# Power_Switching_Circuit_rev3.net
KiCad netlist of a schematic drawn in EAGLE
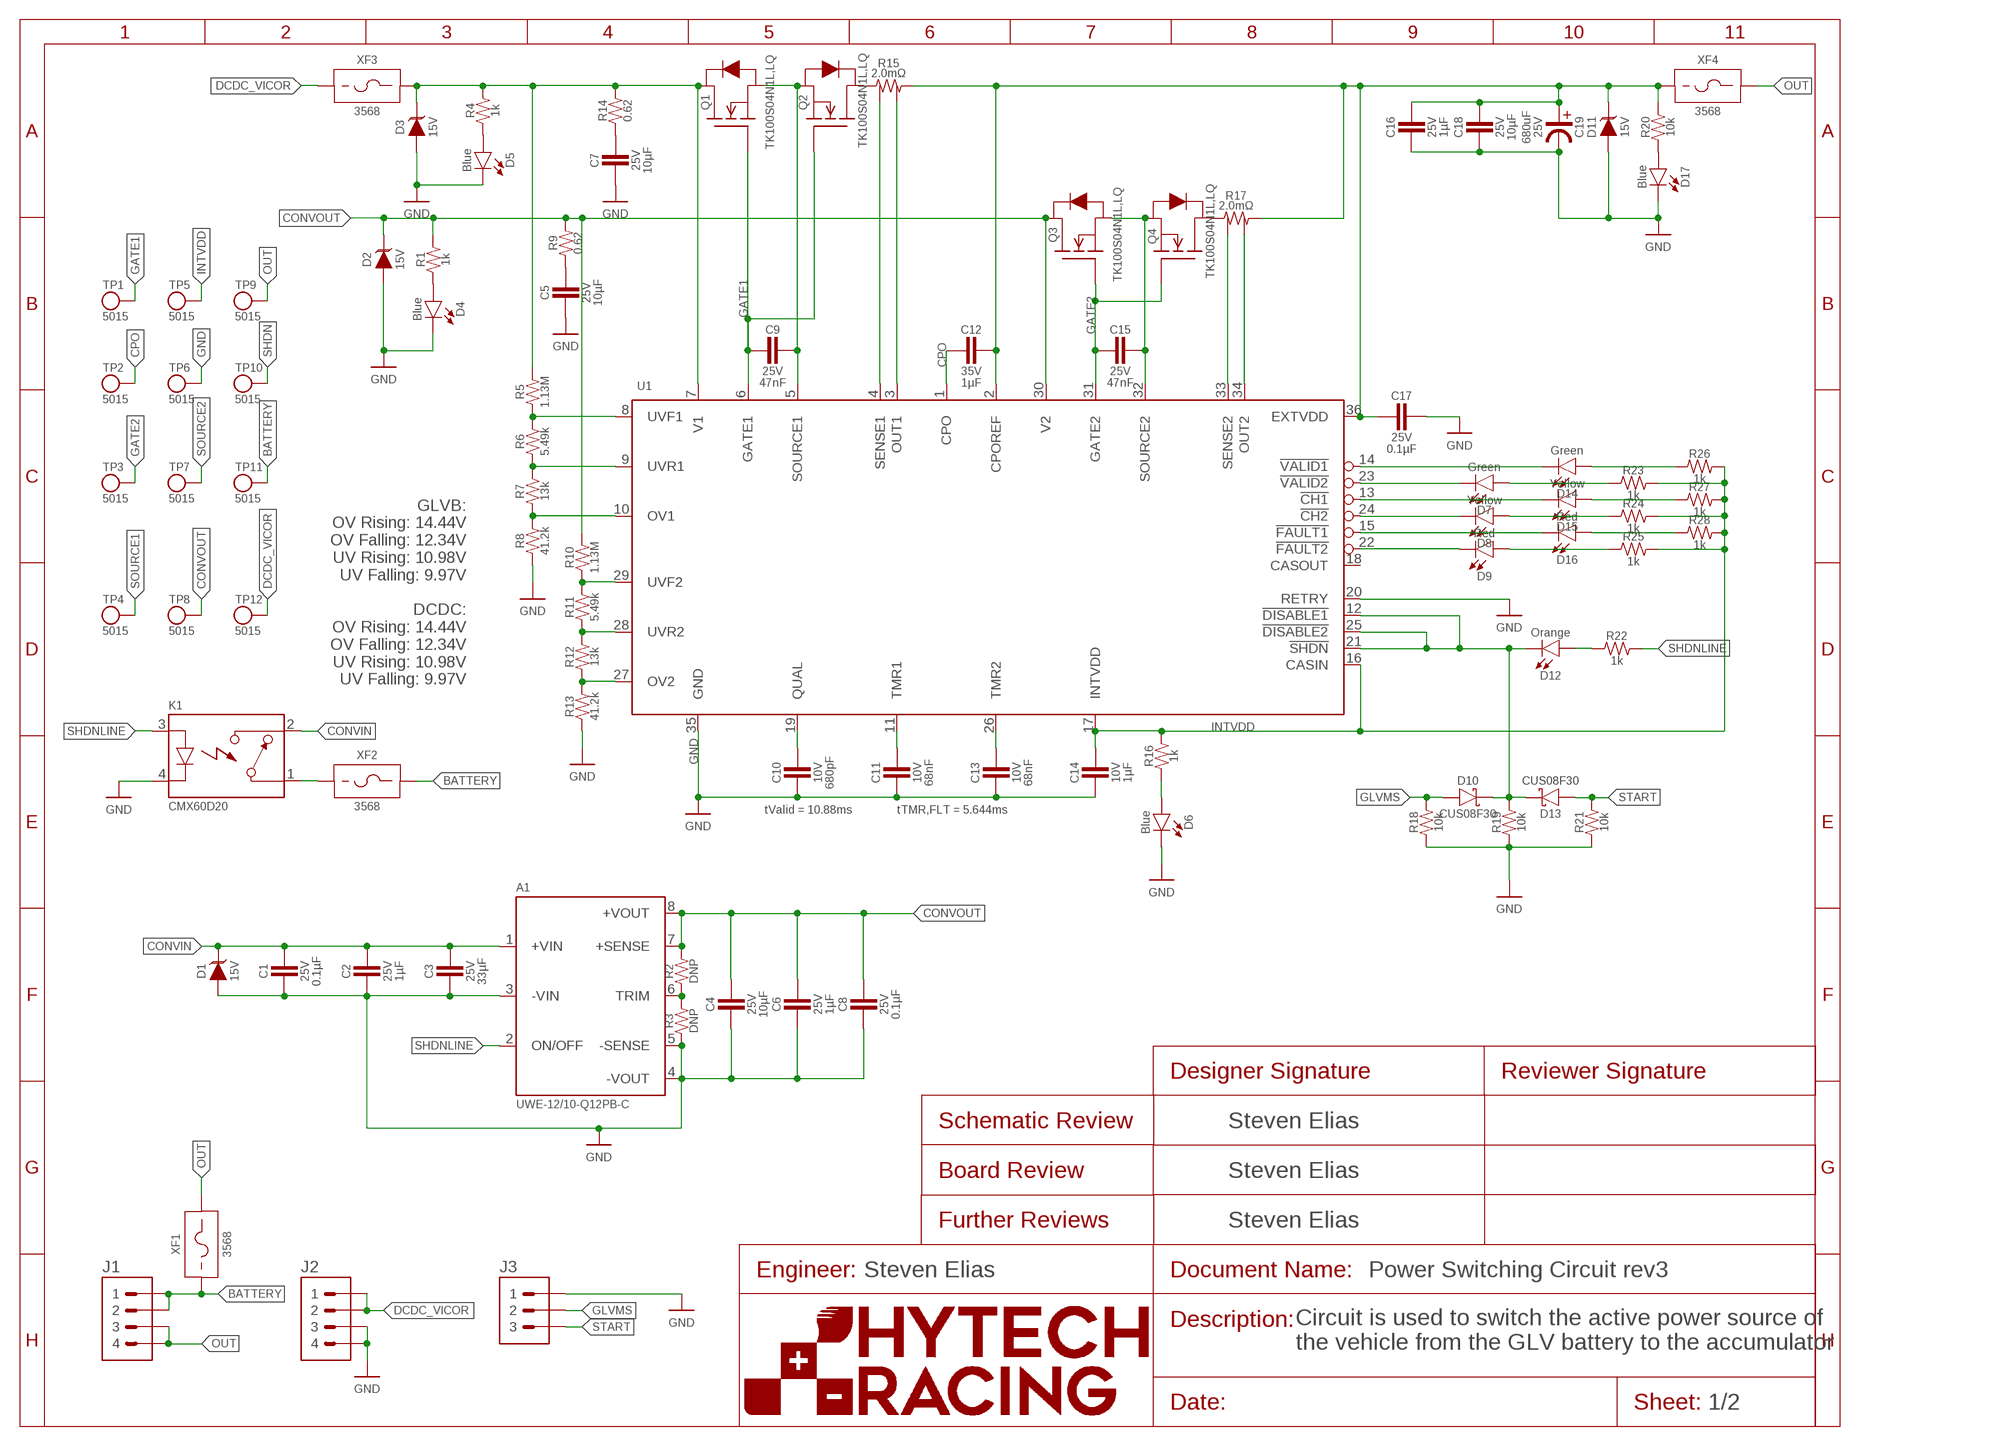
[diagram p0: schematic, sheet 1]
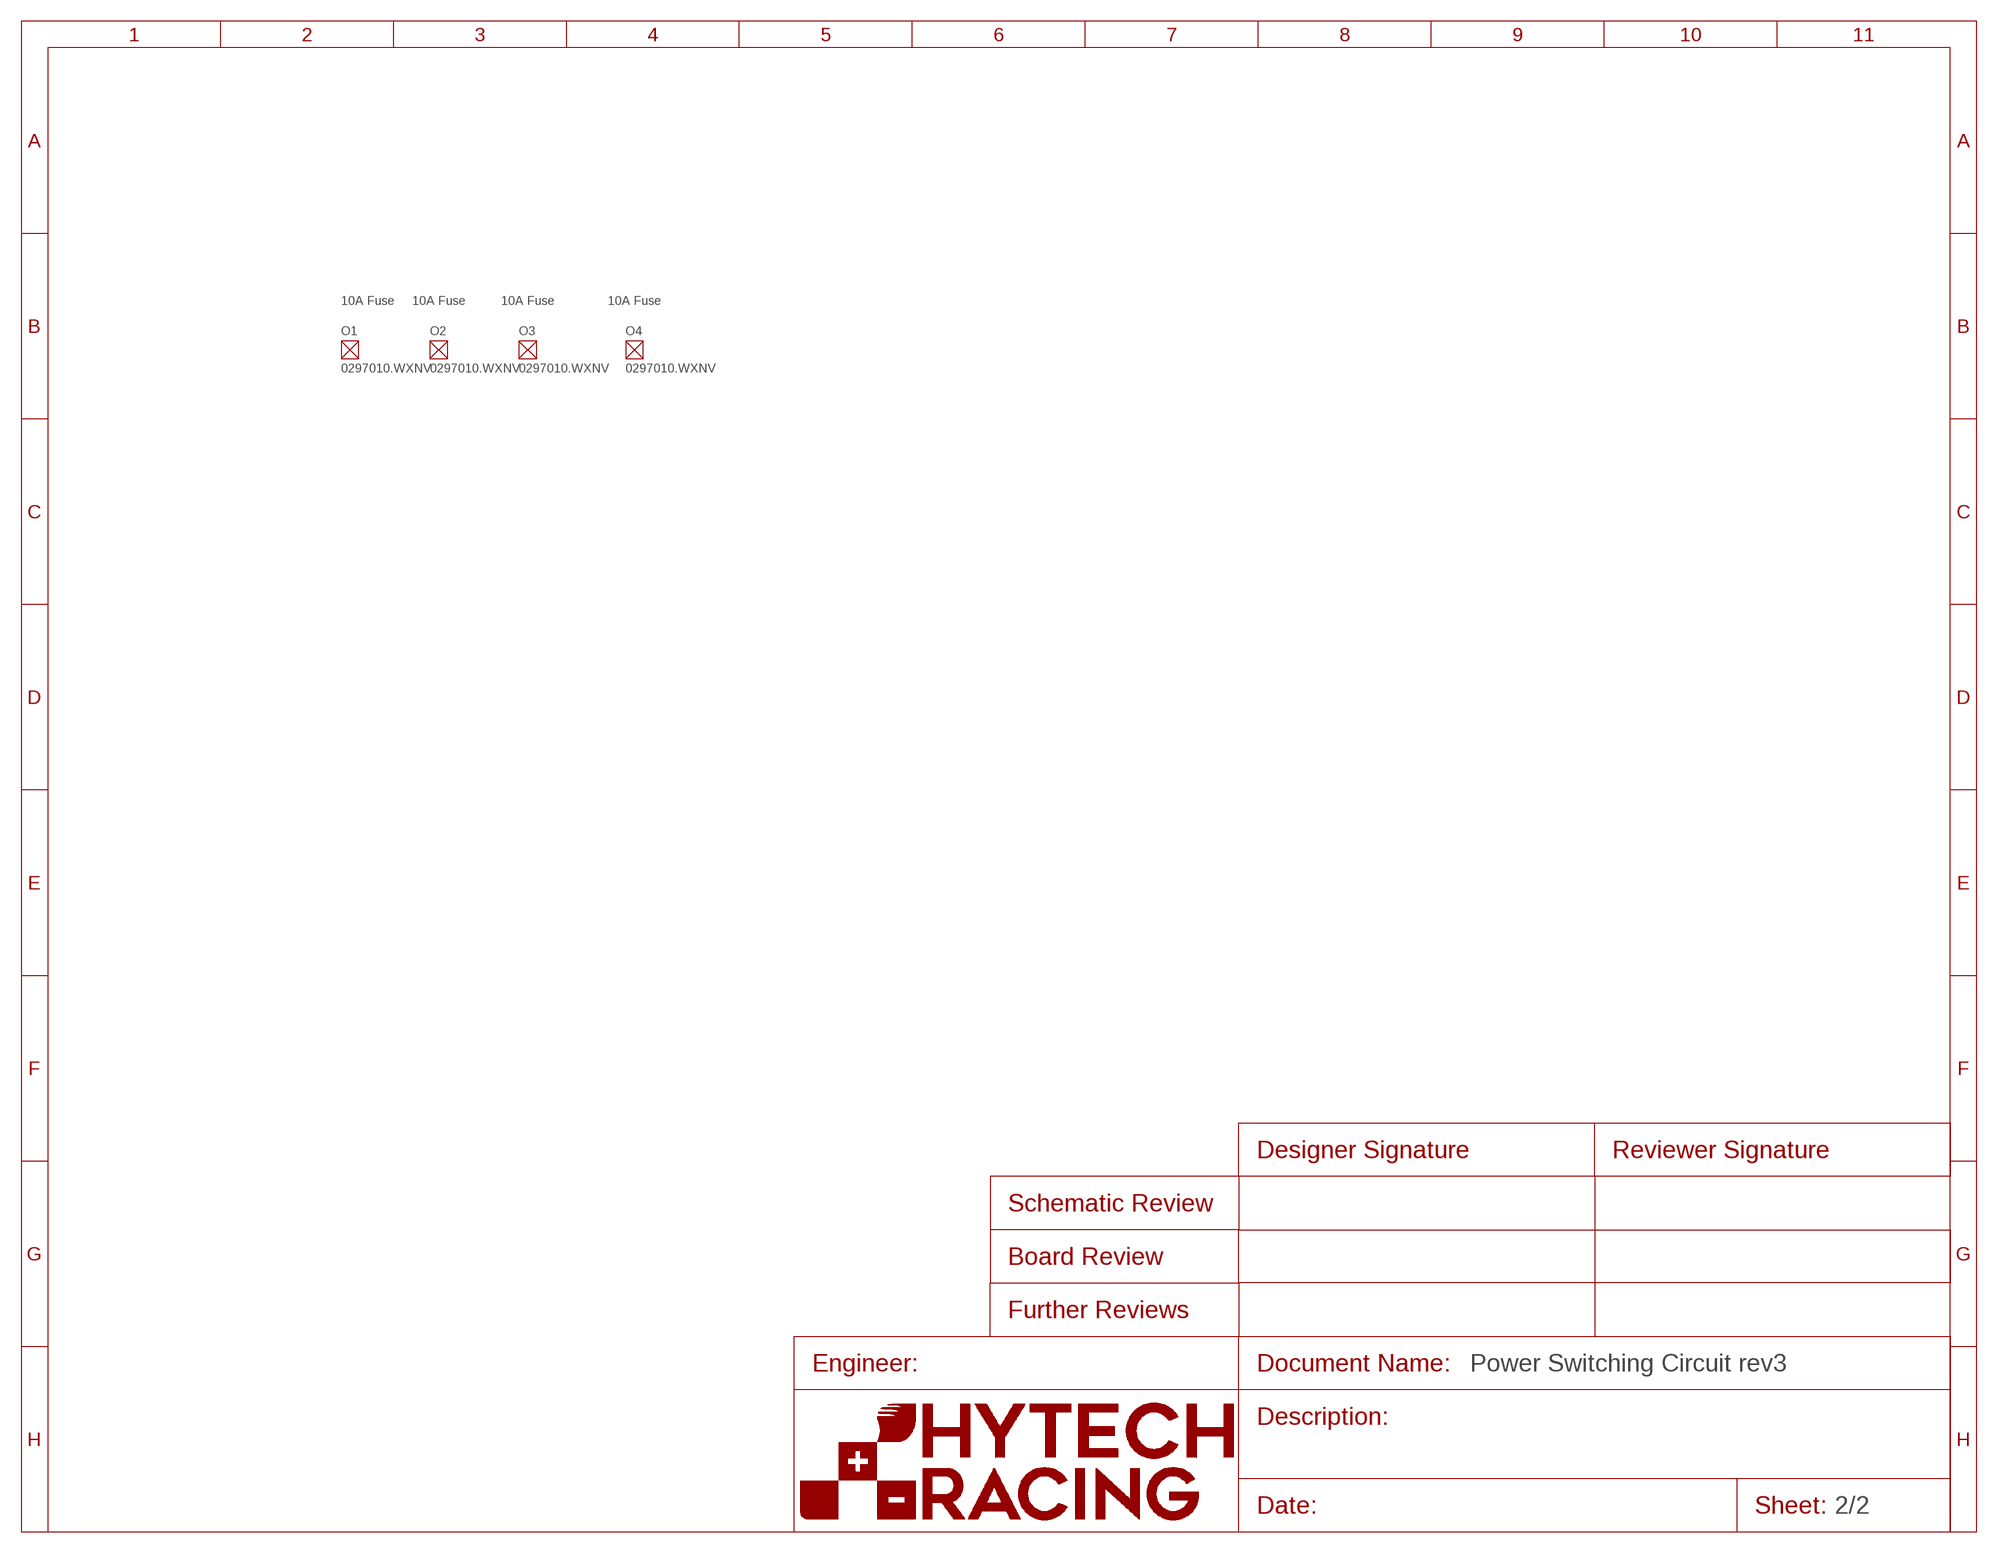
[diagram p1: schematic, sheet 2]

(export (version "E")
  (design (tool "Eeschema 10.0.6"))
  (components
    (comp (ref "A1")
      (value "UWE-12/10-Q12PB-C")
      (footprint "eagle-import:UWE-_")
      (fields
        (field (name "MANUFACTURER") "Murata Power Solutions Inc.")
        (field (name "MPN") "UWE-12/10-Q12PB-C")
      )
      (libsource (lib "eagle-import") (part "UWE-12/10-Q12PB-C"))
    )
    (comp (ref "C1")
      (value "CAPACITOR_0603_25V_0.1UF")
      (footprint "eagle-import:0603-CAP")
      (fields
        (field (name "CAPACITANCE") "0.1µF")
        (field (name "MANUFACTURER") "Samsung Electro-Mechanics")
        (field (name "MPN") "CL10B104KA8NNNC")
        (field (name "TOLERANCE") "10%")
        (field (name "VOLTAGE") "25V")
      )
      (libsource (lib "eagle-import") (part "CAPACITOR_?_060325V_0.1UF"))
    )
    (comp (ref "C2")
      (value "CAPACITOR_0603_25V_1UF")
      (footprint "eagle-import:0603-CAP")
      (fields
        (field (name "CAPACITANCE") "1µF")
        (field (name "MANUFACTURER") "Samsung Electro-Mechanics")
        (field (name "MPN") "CL10B105KA8NNNC")
        (field (name "TOLERANCE") "10%")
        (field (name "VOLTAGE") "25V")
      )
      (libsource (lib "eagle-import") (part "CAPACITOR_?_060325V_1UF"))
    )
    (comp (ref "C3")
      (value "CAPACITOR_1206_25V_33UF")
      (footprint "eagle-import:1206-CAP")
      (fields
        (field (name "CAPACITANCE") "33µF")
        (field (name "MANUFACTURER") "TDK Corporation")
        (field (name "MPN") "C3216X5R1E336M160AC")
        (field (name "TOLERANCE") "20%")
        (field (name "VOLTAGE") "25V")
      )
      (libsource (lib "eagle-import") (part "CAPACITOR_?_120625V_33UF"))
    )
    (comp (ref "C4")
      (value "CAPACITOR_0603_25V_10UF")
      (footprint "eagle-import:0603-CAP")
      (fields
        (field (name "CAPACITANCE") "10µF")
        (field (name "MANUFACTURER") "Murata Electronics")
        (field (name "MPN") "GRM188R61E106MA73D")
        (field (name "TOLERANCE") "20%")
        (field (name "VOLTAGE") "25V")
      )
      (libsource (lib "eagle-import") (part "CAPACITOR_?_060325V_10UF"))
    )
    (comp (ref "C5")
      (value "CAPACITOR_0603_25V_10UF")
      (footprint "eagle-import:0603-CAP")
      (fields
        (field (name "CAPACITANCE") "10µF")
        (field (name "MANUFACTURER") "Murata Electronics")
        (field (name "MPN") "GRM188R61E106MA73D")
        (field (name "TOLERANCE") "20%")
        (field (name "VOLTAGE") "25V")
      )
      (libsource (lib "eagle-import") (part "CAPACITOR_?_060325V_10UF"))
    )
    (comp (ref "C6")
      (value "CAPACITOR_0603_25V_1UF")
      (footprint "eagle-import:0603-CAP")
      (fields
        (field (name "CAPACITANCE") "1µF")
        (field (name "MANUFACTURER") "Samsung Electro-Mechanics")
        (field (name "MPN") "CL10B105KA8NNNC")
        (field (name "TOLERANCE") "10%")
        (field (name "VOLTAGE") "25V")
      )
      (libsource (lib "eagle-import") (part "CAPACITOR_?_060325V_1UF"))
    )
    (comp (ref "C7")
      (value "CAPACITOR_0603_25V_10UF")
      (footprint "eagle-import:0603-CAP")
      (fields
        (field (name "CAPACITANCE") "10µF")
        (field (name "MANUFACTURER") "Murata Electronics")
        (field (name "MPN") "GRM188R61E106MA73D")
        (field (name "TOLERANCE") "20%")
        (field (name "VOLTAGE") "25V")
      )
      (libsource (lib "eagle-import") (part "CAPACITOR_?_060325V_10UF"))
    )
    (comp (ref "C8")
      (value "CAPACITOR_0603_25V_0.1UF")
      (footprint "eagle-import:0603-CAP")
      (fields
        (field (name "CAPACITANCE") "0.1µF")
        (field (name "MANUFACTURER") "Samsung Electro-Mechanics")
        (field (name "MPN") "CL10B104KA8NNNC")
        (field (name "TOLERANCE") "10%")
        (field (name "VOLTAGE") "25V")
      )
      (libsource (lib "eagle-import") (part "CAPACITOR_?_060325V_0.1UF"))
    )
    (comp (ref "C9")
      (value "CAPACITOR_0603_25V_47NF")
      (footprint "eagle-import:0603-CAP")
      (fields
        (field (name "CAPACITANCE") "47nF")
        (field (name "MANUFACTURER") "Kyocera AVX")
        (field (name "MPN") "06033C473K4Z2A")
        (field (name "TOLERANCE") "10%")
        (field (name "VOLTAGE") "25V")
      )
      (libsource (lib "eagle-import") (part "CAPACITOR_?_060325V_47NF"))
    )
    (comp (ref "C10")
      (value "CAPACITOR_0603_10V_680PF")
      (footprint "eagle-import:0603-CAP")
      (fields
        (field (name "CAPACITANCE") "680pF")
        (field (name "MANUFACTURER") "Würth Elektronik")
        (field (name "MPN") "885012006013")
        (field (name "TOLERANCE") "5%")
        (field (name "VOLTAGE") "10V")
      )
      (libsource (lib "eagle-import") (part "CAPACITOR_?_060310V_680PF"))
    )
    (comp (ref "C11")
      (value "CAPACITOR_0603_10V_68NF")
      (footprint "eagle-import:0603-CAP")
      (fields
        (field (name "CAPACITANCE") "68nF")
        (field (name "MANUFACTURER") "KEMET")
        (field (name "MPN") "C0603C683K8RACTU")
        (field (name "TOLERANCE") "10%")
        (field (name "VOLTAGE") "10V")
      )
      (libsource (lib "eagle-import") (part "CAPACITOR_?_060310V_68NF"))
    )
    (comp (ref "C12")
      (value "CAPACITOR_0603_35V_1UF")
      (footprint "eagle-import:0603-CAP")
      (fields
        (field (name "CAPACITANCE") "1µF")
        (field (name "MANUFACTURER") "TDK Corporation")
        (field (name "MPN") "C1608X7R1V105K080AE")
        (field (name "TOLERANCE") "10%")
        (field (name "VOLTAGE") "35V")
      )
      (libsource (lib "eagle-import") (part "CAPACITOR_?_060335V_1UF"))
    )
    (comp (ref "C13")
      (value "CAPACITOR_0603_10V_68NF")
      (footprint "eagle-import:0603-CAP")
      (fields
        (field (name "CAPACITANCE") "68nF")
        (field (name "MANUFACTURER") "KEMET")
        (field (name "MPN") "C0603C683K8RACTU")
        (field (name "TOLERANCE") "10%")
        (field (name "VOLTAGE") "10V")
      )
      (libsource (lib "eagle-import") (part "CAPACITOR_?_060310V_68NF"))
    )
    (comp (ref "C14")
      (value "CAPACITOR_0603_10V_1UF")
      (footprint "eagle-import:0603-CAP")
      (fields
        (field (name "CAPACITANCE") "1µF")
        (field (name "MANUFACTURER") "Yageo")
        (field (name "MPN") "CC0603KRX7R6BB105")
        (field (name "TOLERANCE") "10%")
        (field (name "VOLTAGE") "10V")
      )
      (libsource (lib "eagle-import") (part "CAPACITOR_?_060310V_1UF"))
    )
    (comp (ref "C15")
      (value "CAPACITOR_0603_25V_47NF")
      (footprint "eagle-import:0603-CAP")
      (fields
        (field (name "CAPACITANCE") "47nF")
        (field (name "MANUFACTURER") "Kyocera AVX")
        (field (name "MPN") "06033C473K4Z2A")
        (field (name "TOLERANCE") "10%")
        (field (name "VOLTAGE") "25V")
      )
      (libsource (lib "eagle-import") (part "CAPACITOR_?_060325V_47NF"))
    )
    (comp (ref "C16")
      (value "CAPACITOR_0603_25V_1UF")
      (footprint "eagle-import:0603-CAP")
      (fields
        (field (name "CAPACITANCE") "1µF")
        (field (name "MANUFACTURER") "Samsung Electro-Mechanics")
        (field (name "MPN") "CL10B105KA8NNNC")
        (field (name "TOLERANCE") "10%")
        (field (name "VOLTAGE") "25V")
      )
      (libsource (lib "eagle-import") (part "CAPACITOR_?_060325V_1UF"))
    )
    (comp (ref "C17")
      (value "CAPACITOR_0603_25V_0.1UF")
      (footprint "eagle-import:0603-CAP")
      (fields
        (field (name "CAPACITANCE") "0.1µF")
        (field (name "MANUFACTURER") "Samsung Electro-Mechanics")
        (field (name "MPN") "CL10B104KA8NNNC")
        (field (name "TOLERANCE") "10%")
        (field (name "VOLTAGE") "25V")
      )
      (libsource (lib "eagle-import") (part "CAPACITOR_?_060325V_0.1UF"))
    )
    (comp (ref "C18")
      (value "CAPACITOR_0603_25V_10UF")
      (footprint "eagle-import:0603-CAP")
      (fields
        (field (name "CAPACITANCE") "10µF")
        (field (name "MANUFACTURER") "Murata Electronics")
        (field (name "MPN") "GRM188R61E106MA73D")
        (field (name "TOLERANCE") "20%")
        (field (name "VOLTAGE") "25V")
      )
      (libsource (lib "eagle-import") (part "CAPACITOR_?_060325V_10UF"))
    )
    (comp (ref "C19")
      (value "EEUFP1E681")
      (footprint "eagle-import:EEUFP1E_")
      (fields
        (field (name "CAPACITANCE") "680uF")
        (field (name "MANUFACTURER") "Panasonic Electronic Components")
        (field (name "MPN") "EEU-FP1E681")
        (field (name "TOLERANCE") "20%")
        (field (name "VOLTAGE") "25V")
      )
      (libsource (lib "eagle-import") (part "EEUFP1E681"))
    )
    (comp (ref "D1")
      (value "TVS_15V")
      (footprint "eagle-import:SOT-23")
      (fields
        (field (name "MANUFACTURER") "Vishay General Semiconductor - Diodes Division")
        (field (name "MPN") "GSOT15-E3-08")
        (field (name "VOLTAGE") "15V")
      )
      (libsource (lib "eagle-import") (part "TVS_15V"))
    )
    (comp (ref "D2")
      (value "TVS_15V")
      (footprint "eagle-import:SOT-23")
      (fields
        (field (name "MANUFACTURER") "Vishay General Semiconductor - Diodes Division")
        (field (name "MPN") "GSOT15-E3-08")
        (field (name "VOLTAGE") "15V")
      )
      (libsource (lib "eagle-import") (part "TVS_15V"))
    )
    (comp (ref "D3")
      (value "TVS_15V")
      (footprint "eagle-import:SOT-23")
      (fields
        (field (name "MANUFACTURER") "Vishay General Semiconductor - Diodes Division")
        (field (name "MPN") "GSOT15-E3-08")
        (field (name "VOLTAGE") "15V")
      )
      (libsource (lib "eagle-import") (part "TVS_15V"))
    )
    (comp (ref "D4")
      (value "LED_0603_BLUE")
      (footprint "eagle-import:0603-LED")
      (fields
        (field (name "COLOR") "Blue")
        (field (name "MANUFACTURER") "Kingbright")
        (field (name "MPN") "APT1608VBC/D")
      )
      (libsource (lib "eagle-import") (part "LED_?_0603BLUE"))
    )
    (comp (ref "D5")
      (value "LED_0603_BLUE")
      (footprint "eagle-import:0603-LED")
      (fields
        (field (name "COLOR") "Blue")
        (field (name "MANUFACTURER") "Kingbright")
        (field (name "MPN") "APT1608VBC/D")
      )
      (libsource (lib "eagle-import") (part "LED_?_0603BLUE"))
    )
    (comp (ref "D6")
      (value "LED_0603_BLUE")
      (footprint "eagle-import:0603-LED")
      (fields
        (field (name "COLOR") "Blue")
        (field (name "MANUFACTURER") "Kingbright")
        (field (name "MPN") "APT1608VBC/D")
      )
      (libsource (lib "eagle-import") (part "LED_?_0603BLUE"))
    )
    (comp (ref "D7")
      (value "LED_0603_GREEN")
      (footprint "eagle-import:0603-LED")
      (fields
        (field (name "COLOR") "Green")
        (field (name "MANUFACTURER") "Kingbright")
        (field (name "MPN") "APT1608ZGCK")
      )
      (libsource (lib "eagle-import") (part "LED_?_0603GREEN"))
    )
    (comp (ref "D8")
      (value "LED_0603_YELLOW")
      (footprint "eagle-import:0603-LED")
      (fields
        (field (name "COLOR") "Yellow")
        (field (name "MANUFACTURER") "Kingbright")
        (field (name "MPN") "APT1608SYCK/J3-PRV")
      )
      (libsource (lib "eagle-import") (part "LED_?_0603YELLOW"))
    )
    (comp (ref "D9")
      (value "LED_0603_RED")
      (footprint "eagle-import:0603-LED")
      (fields
        (field (name "COLOR") "Red")
        (field (name "MANUFACTURER") "Kingbright")
        (field (name "MPN") "APT1608SECK/J3-PRV")
      )
      (libsource (lib "eagle-import") (part "LED_?_0603RED"))
    )
    (comp (ref "D10")
      (value "SCHOTTKY_SOD323_30V")
      (footprint "eagle-import:SOD-323")
      (fields
        (field (name "MANUFACTURER") "Toshiba Semiconductor and Storage")
        (field (name "MPN") "CUS08F30")
        (field (name "VOLTAGE") "30V")
      )
      (libsource (lib "eagle-import") (part "SCHOTTKY_?_SOD32330V"))
    )
    (comp (ref "D11")
      (value "TVS_15V")
      (footprint "eagle-import:SOT-23")
      (fields
        (field (name "MANUFACTURER") "Vishay General Semiconductor - Diodes Division")
        (field (name "MPN") "GSOT15-E3-08")
        (field (name "VOLTAGE") "15V")
      )
      (libsource (lib "eagle-import") (part "TVS_15V"))
    )
    (comp (ref "D12")
      (value "LED_0603_ORANGE")
      (footprint "eagle-import:0603-LED")
      (fields
        (field (name "COLOR") "Orange")
        (field (name "MANUFACTURER") "Kingbright")
        (field (name "MPN") "APT1608SECK")
      )
      (libsource (lib "eagle-import") (part "LED_?_0603ORANGE"))
    )
    (comp (ref "D13")
      (value "SCHOTTKY_SOD323_30V")
      (footprint "eagle-import:SOD-323")
      (fields
        (field (name "MANUFACTURER") "Toshiba Semiconductor and Storage")
        (field (name "MPN") "CUS08F30")
        (field (name "VOLTAGE") "30V")
      )
      (libsource (lib "eagle-import") (part "SCHOTTKY_?_SOD32330V"))
    )
    (comp (ref "D14")
      (value "LED_0603_GREEN")
      (footprint "eagle-import:0603-LED")
      (fields
        (field (name "COLOR") "Green")
        (field (name "MANUFACTURER") "Kingbright")
        (field (name "MPN") "APT1608ZGCK")
      )
      (libsource (lib "eagle-import") (part "LED_?_0603GREEN"))
    )
    (comp (ref "D15")
      (value "LED_0603_YELLOW")
      (footprint "eagle-import:0603-LED")
      (fields
        (field (name "COLOR") "Yellow")
        (field (name "MANUFACTURER") "Kingbright")
        (field (name "MPN") "APT1608SYCK/J3-PRV")
      )
      (libsource (lib "eagle-import") (part "LED_?_0603YELLOW"))
    )
    (comp (ref "D16")
      (value "LED_0603_RED")
      (footprint "eagle-import:0603-LED")
      (fields
        (field (name "COLOR") "Red")
        (field (name "MANUFACTURER") "Kingbright")
        (field (name "MPN") "APT1608SECK/J3-PRV")
      )
      (libsource (lib "eagle-import") (part "LED_?_0603RED"))
    )
    (comp (ref "D17")
      (value "LED_0603_BLUE")
      (footprint "eagle-import:0603-LED")
      (fields
        (field (name "COLOR") "Blue")
        (field (name "MANUFACTURER") "Kingbright")
        (field (name "MPN") "APT1608VBC/D")
      )
      (libsource (lib "eagle-import") (part "LED_?_0603BLUE"))
    )
    (comp (ref "J1")
      (value "CONNECTOR-4_SOURIAU_")
      (footprint "eagle-import:SOURIAU_12-04")
      (fields (field (name "MPN") "8STA21204PN") (field (name "MANUFACTURER") "Souriau"))
      (libsource (lib "eagle-import") (part "CONNECTOR-4_?_SOURIAU"))
    )
    (comp (ref "J2")
      (value "CONNECTOR-4_SOURIAU_")
      (footprint "eagle-import:SOURIAU_12-04")
      (fields (field (name "MPN") "8STA21204PN") (field (name "MANUFACTURER") "Souriau"))
      (libsource (lib "eagle-import") (part "CONNECTOR-4_?_SOURIAU"))
    )
    (comp (ref "J3")
      (value "CONNECTOR-3_")
      (footprint "eagle-import:SOURIAU_04-35")
      (libsource (lib "eagle-import") (part "CONNECTOR-3_?"))
    )
    (comp (ref "K1")
      (value "RELAY_SOLIDSTATE_NO_CMX60D20")
      (footprint "eagle-import:CRYDOM_CMX")
      (fields (field (name "MANUFACTURER") "Crydom") (field (name "MPN") "CMX60D20"))
      (libsource (lib "eagle-import") (part "RELAY_SOLIDSTATE_NO_?CMX60D20"))
    )
    (comp (ref "Q1")
      (value "TRANSISTOR_N_MOS_2-7K1S_TK100S04N1LLQ")
      (footprint "eagle-import:DPAK(2-7K1S)")
      (fields
        (field (name "MANUFACTURER") "Toshiba Semiconductor and Storage")
        (field (name "MPN") "TK100S04N1L,LQ")
      )
      (libsource (lib "eagle-import") (part "TRANSISTOR_N_MOS_?_2-7K1STK100S04N1LLQ"))
    )
    (comp (ref "Q2")
      (value "TRANSISTOR_N_MOS_2-7K1S_TK100S04N1LLQ")
      (footprint "eagle-import:DPAK(2-7K1S)")
      (fields
        (field (name "MANUFACTURER") "Toshiba Semiconductor and Storage")
        (field (name "MPN") "TK100S04N1L,LQ")
      )
      (libsource (lib "eagle-import") (part "TRANSISTOR_N_MOS_?_2-7K1STK100S04N1LLQ"))
    )
    (comp (ref "Q3")
      (value "TRANSISTOR_N_MOS_2-7K1S_TK100S04N1LLQ")
      (footprint "eagle-import:DPAK(2-7K1S)")
      (fields
        (field (name "MANUFACTURER") "Toshiba Semiconductor and Storage")
        (field (name "MPN") "TK100S04N1L,LQ")
      )
      (libsource (lib "eagle-import") (part "TRANSISTOR_N_MOS_?_2-7K1STK100S04N1LLQ"))
    )
    (comp (ref "Q4")
      (value "TRANSISTOR_N_MOS_2-7K1S_TK100S04N1LLQ")
      (footprint "eagle-import:DPAK(2-7K1S)")
      (fields
        (field (name "MANUFACTURER") "Toshiba Semiconductor and Storage")
        (field (name "MPN") "TK100S04N1L,LQ")
      )
      (libsource (lib "eagle-import") (part "TRANSISTOR_N_MOS_?_2-7K1STK100S04N1LLQ"))
    )
    (comp (ref "R1")
      (value "RESISTOR_0603_1K")
      (footprint "eagle-import:0603-RES")
      (fields
        (field (name "MANUFACTURER") "Yageo")
        (field (name "MPN") "RC0603FR-071KL")
        (field (name "POWER") "0.1W")
        (field (name "RESISTANCE") "1k")
      )
      (libsource (lib "eagle-import") (part "RESISTOR_?_06031K"))
    )
    (comp (ref "R2")
      (value "RESISTOR_0603_DNP")
      (footprint "eagle-import:0603-RES")
      (fields (field (name "RESISTANCE") "DNP"))
      (libsource (lib "eagle-import") (part "RESISTOR_?_0603DNP"))
    )
    (comp (ref "R3")
      (value "RESISTOR_0603_DNP")
      (footprint "eagle-import:0603-RES")
      (fields (field (name "RESISTANCE") "DNP"))
      (libsource (lib "eagle-import") (part "RESISTOR_?_0603DNP"))
    )
    (comp (ref "R4")
      (value "RESISTOR_0603_1K")
      (footprint "eagle-import:0603-RES")
      (fields
        (field (name "MANUFACTURER") "Yageo")
        (field (name "MPN") "RC0603FR-071KL")
        (field (name "POWER") "0.1W")
        (field (name "RESISTANCE") "1k")
      )
      (libsource (lib "eagle-import") (part "RESISTOR_?_06031K"))
    )
    (comp (ref "R5")
      (value "RESISTOR_0603_1.13M")
      (footprint "eagle-import:0603-RES")
      (fields
        (field (name "MANUFACTURER") "Vishay Dale")
        (field (name "MPN") "CRCW06031M13FKEA")
        (field (name "POWER") "0.1W")
        (field (name "RESISTANCE") "1.13M")
      )
      (libsource (lib "eagle-import") (part "RESISTOR_?_06031.13M"))
    )
    (comp (ref "R6")
      (value "RESISTOR_0603_5.49K")
      (footprint "eagle-import:0603-RES")
      (fields
        (field (name "MANUFACTURER") "Panasonic Electronic Components")
        (field (name "MPN") "ERJ-PB3D5491V")
        (field (name "POWER") "0.2W")
        (field (name "RESISTANCE") "5.49k")
      )
      (libsource (lib "eagle-import") (part "RESISTOR_?_06035.49K"))
    )
    (comp (ref "R7")
      (value "RESISTOR_0603_13K")
      (footprint "eagle-import:0603-RES")
      (fields
        (field (name "MANUFACTURER") "Panasonic Electronic Components")
        (field (name "MPN") "ERA-3ARW133V")
        (field (name "POWER") "0.1W")
        (field (name "RESISTANCE") "13k")
      )
      (libsource (lib "eagle-import") (part "RESISTOR_?_060313K"))
    )
    (comp (ref "R8")
      (value "RESISTOR_0603_41.2K")
      (footprint "eagle-import:0603-RES")
      (fields
        (field (name "MANUFACTURER") "Panasonic Electronic Components")
        (field (name "MPN") " ERJ-PB3B4122V")
        (field (name "POWER") "0.2W")
        (field (name "RESISTANCE") "41.2k")
      )
      (libsource (lib "eagle-import") (part "RESISTOR_?_060341.2K"))
    )
    (comp (ref "R9")
      (value "RESISTOR_0805_0.62")
      (footprint "eagle-import:0805-RES")
      (fields
        (field (name "MANUFACTURER") "Yageo")
        (field (name "MPN") "RL0805FR-070R62L")
        (field (name "POWER") "0.125W")
        (field (name "RESISTANCE") "0.62")
      )
      (libsource (lib "eagle-import") (part "RESISTOR_?_08050.62"))
    )
    (comp (ref "R10")
      (value "RESISTOR_0603_1.13M")
      (footprint "eagle-import:0603-RES")
      (fields
        (field (name "MANUFACTURER") "Vishay Dale")
        (field (name "MPN") "CRCW06031M13FKEA")
        (field (name "POWER") "0.1W")
        (field (name "RESISTANCE") "1.13M")
      )
      (libsource (lib "eagle-import") (part "RESISTOR_?_06031.13M"))
    )
    (comp (ref "R11")
      (value "RESISTOR_0603_5.49K")
      (footprint "eagle-import:0603-RES")
      (fields
        (field (name "MANUFACTURER") "Panasonic Electronic Components")
        (field (name "MPN") "ERJ-PB3D5491V")
        (field (name "POWER") "0.2W")
        (field (name "RESISTANCE") "5.49k")
      )
      (libsource (lib "eagle-import") (part "RESISTOR_?_06035.49K"))
    )
    (comp (ref "R12")
      (value "RESISTOR_0603_13K")
      (footprint "eagle-import:0603-RES")
      (fields
        (field (name "MANUFACTURER") "Panasonic Electronic Components")
        (field (name "MPN") "ERA-3ARW133V")
        (field (name "POWER") "0.1W")
        (field (name "RESISTANCE") "13k")
      )
      (libsource (lib "eagle-import") (part "RESISTOR_?_060313K"))
    )
    (comp (ref "R13")
      (value "RESISTOR_0603_41.2K")
      (footprint "eagle-import:0603-RES")
      (fields
        (field (name "MANUFACTURER") "Panasonic Electronic Components")
        (field (name "MPN") " ERJ-PB3B4122V")
        (field (name "POWER") "0.2W")
        (field (name "RESISTANCE") "41.2k")
      )
      (libsource (lib "eagle-import") (part "RESISTOR_?_060341.2K"))
    )
    (comp (ref "R14")
      (value "RESISTOR_0805_0.62")
      (footprint "eagle-import:0805-RES")
      (fields
        (field (name "MANUFACTURER") "Yageo")
        (field (name "MPN") "RL0805FR-070R62L")
        (field (name "POWER") "0.125W")
        (field (name "RESISTANCE") "0.62")
      )
      (libsource (lib "eagle-import") (part "RESISTOR_?_08050.62"))
    )
    (comp (ref "R15")
      (value "RESISTOR_SENSE__WSL40262L000FEB")
      (footprint "eagle-import:4026")
      (fields
        (field (name "MANUFACTURER") "Vishay Dale")
        (field (name "MPN") "WSL40262L000FEB")
        (field (name "POWER") "3W")
        (field (name "RESISTANCE") "2.0mΩ")
      )
      (libsource (lib "eagle-import") (part "RESISTOR_SENSE_?_WSL40262L000FEB"))
    )
    (comp (ref "R16")
      (value "RESISTOR_0603_1K")
      (footprint "eagle-import:0603-RES")
      (fields
        (field (name "MANUFACTURER") "Yageo")
        (field (name "MPN") "RC0603FR-071KL")
        (field (name "POWER") "0.1W")
        (field (name "RESISTANCE") "1k")
      )
      (libsource (lib "eagle-import") (part "RESISTOR_?_06031K"))
    )
    (comp (ref "R17")
      (value "RESISTOR_SENSE__WSL40262L000FEB")
      (footprint "eagle-import:4026")
      (fields
        (field (name "MANUFACTURER") "Vishay Dale")
        (field (name "MPN") "WSL40262L000FEB")
        (field (name "POWER") "3W")
        (field (name "RESISTANCE") "2.0mΩ")
      )
      (libsource (lib "eagle-import") (part "RESISTOR_SENSE_?_WSL40262L000FEB"))
    )
    (comp (ref "R18")
      (value "RESISTOR_0603_10K")
      (footprint "eagle-import:0603-RES")
      (fields
        (field (name "MANUFACTURER") "Yageo")
        (field (name "MPN") "RC0603FR-0710KL")
        (field (name "POWER") "0.1W")
        (field (name "RESISTANCE") "10k")
      )
      (libsource (lib "eagle-import") (part "RESISTOR_?_060310K"))
    )
    (comp (ref "R19")
      (value "RESISTOR_0603_10K")
      (footprint "eagle-import:0603-RES")
      (fields
        (field (name "MANUFACTURER") "Yageo")
        (field (name "MPN") "RC0603FR-0710KL")
        (field (name "POWER") "0.1W")
        (field (name "RESISTANCE") "10k")
      )
      (libsource (lib "eagle-import") (part "RESISTOR_?_060310K"))
    )
    (comp (ref "R20")
      (value "RESISTOR_0603_10K")
      (footprint "eagle-import:0603-RES")
      (fields
        (field (name "MANUFACTURER") "Yageo")
        (field (name "MPN") "RC0603FR-0710KL")
        (field (name "POWER") "0.1W")
        (field (name "RESISTANCE") "10k")
      )
      (libsource (lib "eagle-import") (part "RESISTOR_?_060310K"))
    )
    (comp (ref "R21")
      (value "RESISTOR_0603_10K")
      (footprint "eagle-import:0603-RES")
      (fields
        (field (name "MANUFACTURER") "Yageo")
        (field (name "MPN") "RC0603FR-0710KL")
        (field (name "POWER") "0.1W")
        (field (name "RESISTANCE") "10k")
      )
      (libsource (lib "eagle-import") (part "RESISTOR_?_060310K"))
    )
    (comp (ref "R22")
      (value "RESISTOR_0603_1K")
      (footprint "eagle-import:0603-RES")
      (fields
        (field (name "MANUFACTURER") "Yageo")
        (field (name "MPN") "RC0603FR-071KL")
        (field (name "POWER") "0.1W")
        (field (name "RESISTANCE") "1k")
      )
      (libsource (lib "eagle-import") (part "RESISTOR_?_06031K"))
    )
    (comp (ref "R23")
      (value "RESISTOR_0603_1K")
      (footprint "eagle-import:0603-RES")
      (fields
        (field (name "MANUFACTURER") "Yageo")
        (field (name "MPN") "RC0603FR-071KL")
        (field (name "POWER") "0.1W")
        (field (name "RESISTANCE") "1k")
      )
      (libsource (lib "eagle-import") (part "RESISTOR_?_06031K"))
    )
    (comp (ref "R24")
      (value "RESISTOR_0603_1K")
      (footprint "eagle-import:0603-RES")
      (fields
        (field (name "MANUFACTURER") "Yageo")
        (field (name "MPN") "RC0603FR-071KL")
        (field (name "POWER") "0.1W")
        (field (name "RESISTANCE") "1k")
      )
      (libsource (lib "eagle-import") (part "RESISTOR_?_06031K"))
    )
    (comp (ref "R25")
      (value "RESISTOR_0603_1K")
      (footprint "eagle-import:0603-RES")
      (fields
        (field (name "MANUFACTURER") "Yageo")
        (field (name "MPN") "RC0603FR-071KL")
        (field (name "POWER") "0.1W")
        (field (name "RESISTANCE") "1k")
      )
      (libsource (lib "eagle-import") (part "RESISTOR_?_06031K"))
    )
    (comp (ref "R26")
      (value "RESISTOR_0603_1K")
      (footprint "eagle-import:0603-RES")
      (fields
        (field (name "MANUFACTURER") "Yageo")
        (field (name "MPN") "RC0603FR-071KL")
        (field (name "POWER") "0.1W")
        (field (name "RESISTANCE") "1k")
      )
      (libsource (lib "eagle-import") (part "RESISTOR_?_06031K"))
    )
    (comp (ref "R27")
      (value "RESISTOR_0603_1K")
      (footprint "eagle-import:0603-RES")
      (fields
        (field (name "MANUFACTURER") "Yageo")
        (field (name "MPN") "RC0603FR-071KL")
        (field (name "POWER") "0.1W")
        (field (name "RESISTANCE") "1k")
      )
      (libsource (lib "eagle-import") (part "RESISTOR_?_06031K"))
    )
    (comp (ref "R28")
      (value "RESISTOR_0603_1K")
      (footprint "eagle-import:0603-RES")
      (fields
        (field (name "MANUFACTURER") "Yageo")
        (field (name "MPN") "RC0603FR-071KL")
        (field (name "POWER") "0.1W")
        (field (name "RESISTANCE") "1k")
      )
      (libsource (lib "eagle-import") (part "RESISTOR_?_06031K"))
    )
    (comp (ref "TP1")
      (value "TEST_POINT")
      (footprint "eagle-import:5015")
      (fields (field (name "MPN") "5015") (field (name "MANUFACTURER") "Keystone Electronics"))
      (libsource (lib "eagle-import") (part "TEST_POINT"))
    )
    (comp (ref "TP2")
      (value "TEST_POINT")
      (footprint "eagle-import:5015")
      (fields (field (name "MPN") "5015") (field (name "MANUFACTURER") "Keystone Electronics"))
      (libsource (lib "eagle-import") (part "TEST_POINT"))
    )
    (comp (ref "TP3")
      (value "TEST_POINT")
      (footprint "eagle-import:5015")
      (fields (field (name "MPN") "5015") (field (name "MANUFACTURER") "Keystone Electronics"))
      (libsource (lib "eagle-import") (part "TEST_POINT"))
    )
    (comp (ref "TP4")
      (value "TEST_POINT")
      (footprint "eagle-import:5015")
      (fields (field (name "MPN") "5015") (field (name "MANUFACTURER") "Keystone Electronics"))
      (libsource (lib "eagle-import") (part "TEST_POINT"))
    )
    (comp (ref "TP5")
      (value "TEST_POINT")
      (footprint "eagle-import:5015")
      (fields (field (name "MPN") "5015") (field (name "MANUFACTURER") "Keystone Electronics"))
      (libsource (lib "eagle-import") (part "TEST_POINT"))
    )
    (comp (ref "TP6")
      (value "TEST_POINT")
      (footprint "eagle-import:5015")
      (fields (field (name "MPN") "5015") (field (name "MANUFACTURER") "Keystone Electronics"))
      (libsource (lib "eagle-import") (part "TEST_POINT"))
    )
    (comp (ref "TP7")
      (value "TEST_POINT")
      (footprint "eagle-import:5015")
      (fields (field (name "MPN") "5015") (field (name "MANUFACTURER") "Keystone Electronics"))
      (libsource (lib "eagle-import") (part "TEST_POINT"))
    )
    (comp (ref "TP8")
      (value "TEST_POINT")
      (footprint "eagle-import:5015")
      (fields (field (name "MPN") "5015") (field (name "MANUFACTURER") "Keystone Electronics"))
      (libsource (lib "eagle-import") (part "TEST_POINT"))
    )
    (comp (ref "TP9")
      (value "TEST_POINT")
      (footprint "eagle-import:5015")
      (fields (field (name "MPN") "5015") (field (name "MANUFACTURER") "Keystone Electronics"))
      (libsource (lib "eagle-import") (part "TEST_POINT"))
    )
    (comp (ref "TP10")
      (value "TEST_POINT")
      (footprint "eagle-import:5015")
      (fields (field (name "MPN") "5015") (field (name "MANUFACTURER") "Keystone Electronics"))
      (libsource (lib "eagle-import") (part "TEST_POINT"))
    )
    (comp (ref "TP11")
      (value "TEST_POINT")
      (footprint "eagle-import:5015")
      (fields (field (name "MPN") "5015") (field (name "MANUFACTURER") "Keystone Electronics"))
      (libsource (lib "eagle-import") (part "TEST_POINT"))
    )
    (comp (ref "TP12")
      (value "TEST_POINT")
      (footprint "eagle-import:5015")
      (fields (field (name "MPN") "5015") (field (name "MANUFACTURER") "Keystone Electronics"))
      (libsource (lib "eagle-import") (part "TEST_POINT"))
    )
    (comp (ref "U1")
      (value "LTC4421")
      (footprint "eagle-import:SSOP-36")
      (fields (field (name "MPN") "LTC4421CG#PBF") (field (name "MANUFACTURER") "Analog Devices Inc."))
      (libsource (lib "eagle-import") (part "LTC4421"))
    )
    (comp (ref "XF1")
      (value "FUSE_HOLDER_MINIBLADEPTH")
      (footprint "eagle-import:3568")
      (fields (field (name "MANUFACTURER") "Keystone") (field (name "MPN") "3568"))
      (libsource (lib "eagle-import") (part "FUSE_HOLDER_PTHMINIBLADE"))
    )
    (comp (ref "XF2")
      (value "FUSE_HOLDER_MINIBLADEPTH")
      (footprint "eagle-import:3568")
      (fields (field (name "MANUFACTURER") "Keystone") (field (name "MPN") "3568"))
      (libsource (lib "eagle-import") (part "FUSE_HOLDER_PTHMINIBLADE"))
    )
    (comp (ref "XF3")
      (value "FUSE_HOLDER_MINIBLADEPTH")
      (footprint "eagle-import:3568")
      (fields (field (name "MANUFACTURER") "Keystone") (field (name "MPN") "3568"))
      (libsource (lib "eagle-import") (part "FUSE_HOLDER_PTHMINIBLADE"))
    )
    (comp (ref "XF4")
      (value "FUSE_HOLDER_MINIBLADEPTH")
      (footprint "eagle-import:3568")
      (fields (field (name "MANUFACTURER") "Keystone") (field (name "MPN") "3568"))
      (libsource (lib "eagle-import") (part "FUSE_HOLDER_PTHMINIBLADE"))
    )
  )
  (nets
    (net (code "1") (name "BATTERY") (class "Default")
      (node (ref "J1") (pin "1") (pinfunction "1_1") (pintype "passive"))
      (node (ref "J1") (pin "2") (pinfunction "2_2") (pintype "passive"))
      (node (ref "TP11") (pin "1") (pinfunction "1_1") (pintype "passive"))
      (node (ref "XF1") (pin "1") (pinfunction "1_1") (pintype "passive"))
      (node (ref "XF1") (pin "2") (pinfunction "1_2") (pintype "passive"))
      (node (ref "XF2") (pin "3") (pinfunction "2_3") (pintype "passive"))
      (node (ref "XF2") (pin "4") (pinfunction "2_4") (pintype "passive"))
    )
    (net (code "2") (name "CONVIN") (class "Default")
      (node (ref "A1") (pin "1") (pinfunction "+VIN_1") (pintype "input"))
      (node (ref "C1") (pin "1") (pinfunction "1_1") (pintype "passive"))
      (node (ref "C2") (pin "1") (pinfunction "1_1") (pintype "passive"))
      (node (ref "C3") (pin "1") (pinfunction "1_1") (pintype "passive"))
      (node (ref "D1") (pin "3") (pinfunction "C_3") (pintype "passive"))
      (node (ref "K1") (pin "2") (pinfunction "CONTACT2_2") (pintype "bidirectional"))
    )
    (net (code "3") (name "CONVOUT") (class "Default")
      (node (ref "A1") (pin "7") (pinfunction "+SENSE_7") (pintype "input"))
      (node (ref "A1") (pin "8") (pinfunction "+VOUT_8") (pintype "power_in"))
      (node (ref "C4") (pin "1") (pinfunction "1_1") (pintype "passive"))
      (node (ref "C6") (pin "1") (pinfunction "1_1") (pintype "passive"))
      (node (ref "C8") (pin "1") (pinfunction "1_1") (pintype "passive"))
      (node (ref "D2") (pin "3") (pinfunction "C_3") (pintype "passive"))
      (node (ref "Q3") (pin "2") (pinfunction "D_2") (pintype "passive"))
      (node (ref "R1") (pin "2") (pinfunction "2_2") (pintype "passive"))
      (node (ref "R10") (pin "2") (pinfunction "2_2") (pintype "passive"))
      (node (ref "R2") (pin "2") (pinfunction "2_2") (pintype "passive"))
      (node (ref "R9") (pin "2") (pinfunction "2_2") (pintype "passive"))
      (node (ref "TP8") (pin "1") (pinfunction "1_1") (pintype "passive"))
      (node (ref "U1") (pin "30") (pinfunction "V2_30") (pintype "input"))
    )
    (net (code "4") (name "CPO") (class "Default")
      (node (ref "C12") (pin "2") (pinfunction "2_2") (pintype "passive"))
      (node (ref "TP2") (pin "1") (pinfunction "1_1") (pintype "passive"))
      (node (ref "U1") (pin "1") (pinfunction "CPO_1") (pintype "input"))
    )
    (net (code "5") (name "DCDC_VICOR") (class "Default")
      (node (ref "J2") (pin "1") (pinfunction "1_1") (pintype "passive"))
      (node (ref "J2") (pin "2") (pinfunction "2_2") (pintype "passive"))
      (node (ref "TP12") (pin "1") (pinfunction "1_1") (pintype "passive"))
      (node (ref "XF3") (pin "1") (pinfunction "1_1") (pintype "passive"))
      (node (ref "XF3") (pin "2") (pinfunction "1_2") (pintype "passive"))
    )
    (net (code "6") (name "GATE1") (class "Default")
      (node (ref "C9") (pin "2") (pinfunction "2_2") (pintype "passive"))
      (node (ref "Q1") (pin "1") (pinfunction "G_1") (pintype "passive"))
      (node (ref "Q2") (pin "1") (pinfunction "G_1") (pintype "passive"))
      (node (ref "TP1") (pin "1") (pinfunction "1_1") (pintype "passive"))
      (node (ref "U1") (pin "6") (pinfunction "GATE1_6") (pintype "input"))
    )
    (net (code "7") (name "GATE2") (class "Default")
      (node (ref "C15") (pin "2") (pinfunction "2_2") (pintype "passive"))
      (node (ref "Q3") (pin "1") (pinfunction "G_1") (pintype "passive"))
      (node (ref "Q4") (pin "1") (pinfunction "G_1") (pintype "passive"))
      (node (ref "TP3") (pin "1") (pinfunction "1_1") (pintype "passive"))
      (node (ref "U1") (pin "31") (pinfunction "GATE2_31") (pintype "input"))
    )
    (net (code "8") (name "GLVMS") (class "Default")
      (node (ref "D10") (pin "A") (pinfunction "A_A") (pintype "passive"))
      (node (ref "J3") (pin "B") (pinfunction "2_B") (pintype "passive"))
      (node (ref "R18") (pin "2") (pinfunction "2_2") (pintype "passive"))
    )
    (net (code "9") (name "GND") (class "Default")
      (node (ref "A1") (pin "3") (pinfunction "-VIN_3") (pintype "input"))
      (node (ref "A1") (pin "4") (pinfunction "-VOUT_4") (pintype "power_in"))
      (node (ref "A1") (pin "5") (pinfunction "-SENSE_5") (pintype "input"))
      (node (ref "C1") (pin "2") (pinfunction "2_2") (pintype "passive"))
      (node (ref "C10") (pin "2") (pinfunction "2_2") (pintype "passive"))
      (node (ref "C11") (pin "2") (pinfunction "2_2") (pintype "passive"))
      (node (ref "C13") (pin "2") (pinfunction "2_2") (pintype "passive"))
      (node (ref "C14") (pin "2") (pinfunction "2_2") (pintype "passive"))
      (node (ref "C16") (pin "2") (pinfunction "2_2") (pintype "passive"))
      (node (ref "C17") (pin "1") (pinfunction "1_1") (pintype "passive"))
      (node (ref "C18") (pin "2") (pinfunction "2_2") (pintype "passive"))
      (node (ref "C19") (pin "P$2") (pinfunction "MINUS_P$2") (pintype "passive"))
      (node (ref "C2") (pin "2") (pinfunction "2_2") (pintype "passive"))
      (node (ref "C3") (pin "2") (pinfunction "2_2") (pintype "passive"))
      (node (ref "C4") (pin "2") (pinfunction "2_2") (pintype "passive"))
      (node (ref "C5") (pin "2") (pinfunction "2_2") (pintype "passive"))
      (node (ref "C6") (pin "2") (pinfunction "2_2") (pintype "passive"))
      (node (ref "C7") (pin "2") (pinfunction "2_2") (pintype "passive"))
      (node (ref "C8") (pin "2") (pinfunction "2_2") (pintype "passive"))
      (node (ref "D1") (pin "1") (pinfunction "A_1") (pintype "passive"))
      (node (ref "D11") (pin "1") (pinfunction "A_1") (pintype "passive"))
      (node (ref "D17") (pin "1") (pinfunction "C_1") (pintype "passive"))
      (node (ref "D2") (pin "1") (pinfunction "A_1") (pintype "passive"))
      (node (ref "D3") (pin "1") (pinfunction "A_1") (pintype "passive"))
      (node (ref "D4") (pin "1") (pinfunction "C_1") (pintype "passive"))
      (node (ref "D5") (pin "1") (pinfunction "C_1") (pintype "passive"))
      (node (ref "D6") (pin "1") (pinfunction "C_1") (pintype "passive"))
      (node (ref "J2") (pin "3") (pinfunction "3_3") (pintype "passive"))
      (node (ref "J2") (pin "4") (pinfunction "4_4") (pintype "passive"))
      (node (ref "J3") (pin "A") (pinfunction "1_A") (pintype "passive"))
      (node (ref "K1") (pin "4") (pinfunction "CONTROL-_4") (pintype "passive"))
      (node (ref "R13") (pin "1") (pinfunction "1_1") (pintype "passive"))
      (node (ref "R18") (pin "1") (pinfunction "1_1") (pintype "passive"))
      (node (ref "R19") (pin "1") (pinfunction "1_1") (pintype "passive"))
      (node (ref "R21") (pin "1") (pinfunction "1_1") (pintype "passive"))
      (node (ref "R3") (pin "1") (pinfunction "1_1") (pintype "passive"))
      (node (ref "R8") (pin "1") (pinfunction "1_1") (pintype "passive"))
      (node (ref "TP6") (pin "1") (pinfunction "1_1") (pintype "passive"))
      (node (ref "U1") (pin "20") (pinfunction "RETRY_20") (pintype "input"))
      (node (ref "U1") (pin "35") (pinfunction "GND_35") (pintype "power_in"))
    )
    (net (code "10") (name "INTVDD") (class "Default")
      (node (ref "C14") (pin "1") (pinfunction "1_1") (pintype "passive"))
      (node (ref "R16") (pin "2") (pinfunction "2_2") (pintype "passive"))
      (node (ref "R23") (pin "2") (pinfunction "2_2") (pintype "passive"))
      (node (ref "R24") (pin "2") (pinfunction "2_2") (pintype "passive"))
      (node (ref "R25") (pin "2") (pinfunction "2_2") (pintype "passive"))
      (node (ref "R26") (pin "2") (pinfunction "2_2") (pintype "passive"))
      (node (ref "R27") (pin "2") (pinfunction "2_2") (pintype "passive"))
      (node (ref "R28") (pin "2") (pinfunction "2_2") (pintype "passive"))
      (node (ref "TP5") (pin "1") (pinfunction "1_1") (pintype "passive"))
      (node (ref "U1") (pin "16") (pinfunction "CASIN_16") (pintype "input"))
      (node (ref "U1") (pin "17") (pinfunction "INTVDD_17") (pintype "power_in"))
    )
    (net (code "11") (name "Net-(A1-TRIM)") (class "Default")
      (node (ref "A1") (pin "6") (pinfunction "TRIM_6") (pintype "input"))
      (node (ref "R2") (pin "1") (pinfunction "1_1") (pintype "passive"))
      (node (ref "R3") (pin "2") (pinfunction "2_2") (pintype "passive"))
    )
    (net (code "12") (name "Net-(C5-Pad1)") (class "Default")
      (node (ref "C5") (pin "1") (pinfunction "1_1") (pintype "passive"))
      (node (ref "R9") (pin "1") (pinfunction "1_1") (pintype "passive"))
    )
    (net (code "13") (name "Net-(C7-Pad1)") (class "Default")
      (node (ref "C7") (pin "1") (pinfunction "1_1") (pintype "passive"))
      (node (ref "R14") (pin "1") (pinfunction "1_1") (pintype "passive"))
    )
    (net (code "14") (name "Net-(C19-PLUS)") (class "Default")
      (node (ref "C12") (pin "1") (pinfunction "1_1") (pintype "passive"))
      (node (ref "C16") (pin "1") (pinfunction "1_1") (pintype "passive"))
      (node (ref "C17") (pin "2") (pinfunction "2_2") (pintype "passive"))
      (node (ref "C18") (pin "1") (pinfunction "1_1") (pintype "passive"))
      (node (ref "C19") (pin "P$1") (pinfunction "PLUS_P$1") (pintype "passive"))
      (node (ref "D11") (pin "3") (pinfunction "C_3") (pintype "passive"))
      (node (ref "R15") (pin "2") (pinfunction "2_2") (pintype "passive"))
      (node (ref "R17") (pin "2") (pinfunction "2_2") (pintype "passive"))
      (node (ref "R20") (pin "2") (pinfunction "2_2") (pintype "passive"))
      (node (ref "U1") (pin "2") (pinfunction "CPOREF_2") (pintype "input"))
      (node (ref "U1") (pin "36") (pinfunction "EXTVDD_36") (pintype "power_in"))
      (node (ref "XF4") (pin "1") (pinfunction "1_1") (pintype "passive"))
      (node (ref "XF4") (pin "2") (pinfunction "1_2") (pintype "passive"))
    )
    (net (code "15") (name "Net-(D3-C)") (class "Default")
      (node (ref "D3") (pin "3") (pinfunction "C_3") (pintype "passive"))
      (node (ref "Q1") (pin "2") (pinfunction "D_2") (pintype "passive"))
      (node (ref "R14") (pin "2") (pinfunction "2_2") (pintype "passive"))
      (node (ref "R4") (pin "2") (pinfunction "2_2") (pintype "passive"))
      (node (ref "R5") (pin "2") (pinfunction "2_2") (pintype "passive"))
      (node (ref "U1") (pin "7") (pinfunction "V1_7") (pintype "input"))
      (node (ref "XF3") (pin "3") (pinfunction "2_3") (pintype "passive"))
      (node (ref "XF3") (pin "4") (pinfunction "2_4") (pintype "passive"))
    )
    (net (code "16") (name "Net-(D4-A)") (class "Default")
      (node (ref "D4") (pin "2") (pinfunction "A_2") (pintype "passive"))
      (node (ref "R1") (pin "1") (pinfunction "1_1") (pintype "passive"))
    )
    (net (code "17") (name "Net-(D5-A)") (class "Default")
      (node (ref "D5") (pin "2") (pinfunction "A_2") (pintype "passive"))
      (node (ref "R4") (pin "1") (pinfunction "1_1") (pintype "passive"))
    )
    (net (code "18") (name "Net-(D6-A)") (class "Default")
      (node (ref "D6") (pin "2") (pinfunction "A_2") (pintype "passive"))
      (node (ref "R16") (pin "1") (pinfunction "1_1") (pintype "passive"))
    )
    (net (code "19") (name "Net-(D7-A)") (class "Default")
      (node (ref "D7") (pin "2") (pinfunction "A_2") (pintype "passive"))
      (node (ref "R23") (pin "1") (pinfunction "1_1") (pintype "passive"))
    )
    (net (code "20") (name "Net-(D7-C)") (class "Default")
      (node (ref "D7") (pin "1") (pinfunction "C_1") (pintype "passive"))
      (node (ref "U1") (pin "23") (pinfunction "~{VALID2}_23") (pintype "open_collector"))
    )
    (net (code "21") (name "Net-(D8-A)") (class "Default")
      (node (ref "D8") (pin "2") (pinfunction "A_2") (pintype "passive"))
      (node (ref "R24") (pin "1") (pinfunction "1_1") (pintype "passive"))
    )
    (net (code "22") (name "Net-(D8-C)") (class "Default")
      (node (ref "D8") (pin "1") (pinfunction "C_1") (pintype "passive"))
      (node (ref "U1") (pin "24") (pinfunction "~{CH2}_24") (pintype "open_collector"))
    )
    (net (code "23") (name "Net-(D9-A)") (class "Default")
      (node (ref "D9") (pin "2") (pinfunction "A_2") (pintype "passive"))
      (node (ref "R25") (pin "1") (pinfunction "1_1") (pintype "passive"))
    )
    (net (code "24") (name "Net-(D9-C)") (class "Default")
      (node (ref "D9") (pin "1") (pinfunction "C_1") (pintype "passive"))
      (node (ref "U1") (pin "22") (pinfunction "~{FAULT2}_22") (pintype "open_collector"))
    )
    (net (code "25") (name "Net-(D12-A)") (class "Default")
      (node (ref "D12") (pin "2") (pinfunction "A_2") (pintype "passive"))
      (node (ref "R22") (pin "1") (pinfunction "1_1") (pintype "passive"))
    )
    (net (code "26") (name "Net-(D14-A)") (class "Default")
      (node (ref "D14") (pin "2") (pinfunction "A_2") (pintype "passive"))
      (node (ref "R26") (pin "1") (pinfunction "1_1") (pintype "passive"))
    )
    (net (code "27") (name "Net-(D14-C)") (class "Default")
      (node (ref "D14") (pin "1") (pinfunction "C_1") (pintype "passive"))
      (node (ref "U1") (pin "14") (pinfunction "~{VALID1}_14") (pintype "open_collector"))
    )
    (net (code "28") (name "Net-(D15-A)") (class "Default")
      (node (ref "D15") (pin "2") (pinfunction "A_2") (pintype "passive"))
      (node (ref "R27") (pin "1") (pinfunction "1_1") (pintype "passive"))
    )
    (net (code "29") (name "Net-(D15-C)") (class "Default")
      (node (ref "D15") (pin "1") (pinfunction "C_1") (pintype "passive"))
      (node (ref "U1") (pin "13") (pinfunction "~{CH1}_13") (pintype "open_collector"))
    )
    (net (code "30") (name "Net-(D16-A)") (class "Default")
      (node (ref "D16") (pin "2") (pinfunction "A_2") (pintype "passive"))
      (node (ref "R28") (pin "1") (pinfunction "1_1") (pintype "passive"))
    )
    (net (code "31") (name "Net-(D16-C)") (class "Default")
      (node (ref "D16") (pin "1") (pinfunction "C_1") (pintype "passive"))
      (node (ref "U1") (pin "15") (pinfunction "~{FAULT1}_15") (pintype "open_collector"))
    )
    (net (code "32") (name "Net-(D17-A)") (class "Default")
      (node (ref "D17") (pin "2") (pinfunction "A_2") (pintype "passive"))
      (node (ref "R20") (pin "1") (pinfunction "1_1") (pintype "passive"))
    )
    (net (code "33") (name "Net-(K1-CONTACT1)") (class "Default")
      (node (ref "K1") (pin "1") (pinfunction "CONTACT1_1") (pintype "bidirectional"))
      (node (ref "XF2") (pin "1") (pinfunction "1_1") (pintype "passive"))
      (node (ref "XF2") (pin "2") (pinfunction "1_2") (pintype "passive"))
    )
    (net (code "34") (name "Net-(Q2-D)") (class "Default")
      (node (ref "Q2") (pin "2") (pinfunction "D_2") (pintype "passive"))
      (node (ref "R15") (pin "1") (pinfunction "1_1") (pintype "passive"))
    )
    (net (code "35") (name "Net-(Q4-D)") (class "Default")
      (node (ref "Q4") (pin "2") (pinfunction "D_2") (pintype "passive"))
      (node (ref "R17") (pin "1") (pinfunction "1_1") (pintype "passive"))
    )
    (net (code "36") (name "Net-(U1-OUT1)") (class "Default")
      (node (ref "R15") (pin "4") (pinfunction "4_4") (pintype "passive"))
      (node (ref "U1") (pin "3") (pinfunction "OUT1_3") (pintype "input"))
    )
    (net (code "37") (name "Net-(U1-OUT2)") (class "Default")
      (node (ref "R17") (pin "4") (pinfunction "4_4") (pintype "passive"))
      (node (ref "U1") (pin "34") (pinfunction "OUT2_34") (pintype "input"))
    )
    (net (code "38") (name "Net-(U1-OV1)") (class "Default")
      (node (ref "R7") (pin "1") (pinfunction "1_1") (pintype "passive"))
      (node (ref "R8") (pin "2") (pinfunction "2_2") (pintype "passive"))
      (node (ref "U1") (pin "10") (pinfunction "OV1_10") (pintype "input"))
    )
    (net (code "39") (name "Net-(U1-OV2)") (class "Default")
      (node (ref "R12") (pin "1") (pinfunction "1_1") (pintype "passive"))
      (node (ref "R13") (pin "2") (pinfunction "2_2") (pintype "passive"))
      (node (ref "U1") (pin "27") (pinfunction "OV2_27") (pintype "input"))
    )
    (net (code "40") (name "Net-(U1-QUAL)") (class "Default")
      (node (ref "C10") (pin "1") (pinfunction "1_1") (pintype "passive"))
      (node (ref "U1") (pin "19") (pinfunction "QUAL_19") (pintype "bidirectional"))
    )
    (net (code "41") (name "Net-(U1-SENSE1)") (class "Default")
      (node (ref "R15") (pin "3") (pinfunction "3_3") (pintype "passive"))
      (node (ref "U1") (pin "4") (pinfunction "SENSE1_4") (pintype "input"))
    )
    (net (code "42") (name "Net-(U1-SENSE2)") (class "Default")
      (node (ref "R17") (pin "3") (pinfunction "3_3") (pintype "passive"))
      (node (ref "U1") (pin "33") (pinfunction "SENSE2_33") (pintype "input"))
    )
    (net (code "43") (name "Net-(U1-TMR1)") (class "Default")
      (node (ref "C11") (pin "1") (pinfunction "1_1") (pintype "passive"))
      (node (ref "U1") (pin "11") (pinfunction "TMR1_11") (pintype "bidirectional"))
    )
    (net (code "44") (name "Net-(U1-TMR2)") (class "Default")
      (node (ref "C13") (pin "1") (pinfunction "1_1") (pintype "passive"))
      (node (ref "U1") (pin "26") (pinfunction "TMR2_26") (pintype "bidirectional"))
    )
    (net (code "45") (name "Net-(U1-UVF1)") (class "Default")
      (node (ref "R5") (pin "1") (pinfunction "1_1") (pintype "passive"))
      (node (ref "R6") (pin "2") (pinfunction "2_2") (pintype "passive"))
      (node (ref "U1") (pin "8") (pinfunction "UVF1_8") (pintype "input"))
    )
    (net (code "46") (name "Net-(U1-UVF2)") (class "Default")
      (node (ref "R10") (pin "1") (pinfunction "1_1") (pintype "passive"))
      (node (ref "R11") (pin "2") (pinfunction "2_2") (pintype "passive"))
      (node (ref "U1") (pin "29") (pinfunction "UVF2_29") (pintype "input"))
    )
    (net (code "47") (name "Net-(U1-UVR1)") (class "Default")
      (node (ref "R6") (pin "1") (pinfunction "1_1") (pintype "passive"))
      (node (ref "R7") (pin "2") (pinfunction "2_2") (pintype "passive"))
      (node (ref "U1") (pin "9") (pinfunction "UVR1_9") (pintype "input"))
    )
    (net (code "48") (name "Net-(U1-UVR2)") (class "Default")
      (node (ref "R11") (pin "1") (pinfunction "1_1") (pintype "passive"))
      (node (ref "R12") (pin "2") (pinfunction "2_2") (pintype "passive"))
      (node (ref "U1") (pin "28") (pinfunction "UVR2_28") (pintype "input"))
    )
    (net (code "49") (name "OUT") (class "Default")
      (node (ref "J1") (pin "3") (pinfunction "3_3") (pintype "passive"))
      (node (ref "J1") (pin "4") (pinfunction "4_4") (pintype "passive"))
      (node (ref "TP9") (pin "1") (pinfunction "1_1") (pintype "passive"))
      (node (ref "XF1") (pin "3") (pinfunction "2_3") (pintype "passive"))
      (node (ref "XF1") (pin "4") (pinfunction "2_4") (pintype "passive"))
      (node (ref "XF4") (pin "3") (pinfunction "2_3") (pintype "passive"))
      (node (ref "XF4") (pin "4") (pinfunction "2_4") (pintype "passive"))
    )
    (net (code "50") (name "SHDN") (class "Default")
      (node (ref "D10") (pin "C") (pinfunction "C_C") (pintype "passive"))
      (node (ref "D12") (pin "1") (pinfunction "C_1") (pintype "passive"))
      (node (ref "D13") (pin "C") (pinfunction "C_C") (pintype "passive"))
      (node (ref "R19") (pin "2") (pinfunction "2_2") (pintype "passive"))
      (node (ref "TP10") (pin "1") (pinfunction "1_1") (pintype "passive"))
      (node (ref "U1") (pin "12") (pinfunction "~{DISABLE1}_12") (pintype "input"))
      (node (ref "U1") (pin "21") (pinfunction "~{SHDN}_21") (pintype "input"))
      (node (ref "U1") (pin "25") (pinfunction "~{DISABLE2}_25") (pintype "input"))
    )
    (net (code "51") (name "SHDNLINE") (class "Default")
      (node (ref "A1") (pin "2") (pinfunction "ON/OFF_2") (pintype "input"))
      (node (ref "K1") (pin "3") (pinfunction "CONTROL+_3") (pintype "passive"))
      (node (ref "R22") (pin "2") (pinfunction "2_2") (pintype "passive"))
    )
    (net (code "52") (name "SOURCE1") (class "Default")
      (node (ref "C9") (pin "1") (pinfunction "1_1") (pintype "passive"))
      (node (ref "Q1") (pin "3") (pinfunction "S_3") (pintype "passive"))
      (node (ref "Q2") (pin "3") (pinfunction "S_3") (pintype "passive"))
      (node (ref "TP4") (pin "1") (pinfunction "1_1") (pintype "passive"))
      (node (ref "U1") (pin "5") (pinfunction "SOURCE1_5") (pintype "input"))
    )
    (net (code "53") (name "SOURCE2") (class "Default")
      (node (ref "C15") (pin "1") (pinfunction "1_1") (pintype "passive"))
      (node (ref "Q3") (pin "3") (pinfunction "S_3") (pintype "passive"))
      (node (ref "Q4") (pin "3") (pinfunction "S_3") (pintype "passive"))
      (node (ref "TP7") (pin "1") (pinfunction "1_1") (pintype "passive"))
      (node (ref "U1") (pin "32") (pinfunction "SOURCE2_32") (pintype "input"))
    )
    (net (code "54") (name "START") (class "Default")
      (node (ref "D13") (pin "A") (pinfunction "A_A") (pintype "passive"))
      (node (ref "J3") (pin "C") (pinfunction "3_C") (pintype "passive"))
      (node (ref "R21") (pin "2") (pinfunction "2_2") (pintype "passive"))
    )
    (net (code "55") (name "unconnected-(U1-CASOUT-Pad18)") (class "Default")
      (node (ref "U1") (pin "18") (pinfunction "CASOUT_18") (pintype "output"))
    )
  )
)
